# ThePixelExpert_ESP-32-WLED-Board__PCB__S.net
KiCad netlist of a schematic drawn in Altium Designer
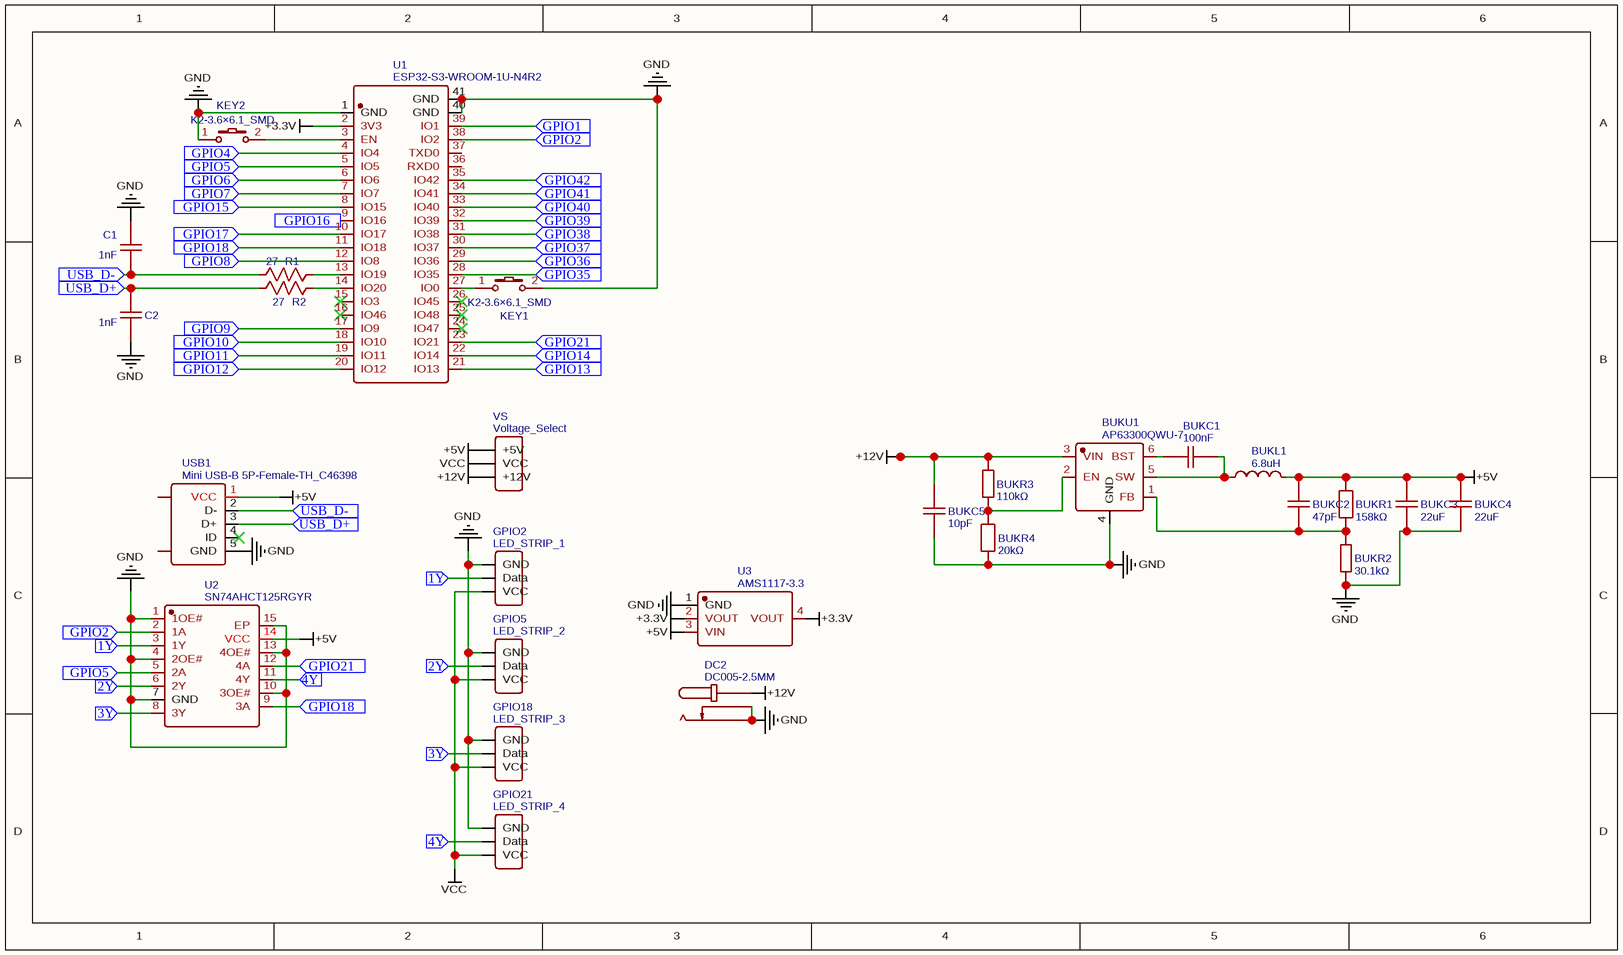
[diagram p0: ThePixelExpert_ESP-32-WLED-Board__PCB__Sheet_1_2025-09-09.schdoc]

(export (version "E")
  (design (tool "Eeschema 10.0.6"))
  (components
    (comp (ref "BUKC1")
      (value "100nF")
      (fields
        (field (name "MANUFACTURER") "FH(风华)")
        (field (name "MANUFACTURER PART") "0603B104J250NT")
        (field (name "CONTRIBUTOR") "lcsc")
      )
      (libsource (lib "altium-import") (part "root_0_100nF_"))
    )
    (comp (ref "BUKC2")
      (value "47pF")
      (fields
        (field (name "MANUFACTURER") "AIDE(爱迪电容)")
        (field (name "MANUFACTURER PART") "0603C0G470J500NT")
        (field (name "CONTRIBUTOR") "lcsc")
      )
      (libsource (lib "altium-import") (part "root_1_47pF_"))
    )
    (comp (ref "BUKC3")
      (value "22uF")
      (fields
        (field (name "MANUFACTURER") "Chinocera(华瓷)")
        (field (name "MANUFACTURER PART") "HGC0603R5226M160NTHJ")
        (field (name "CONTRIBUTOR") "lcsc")
      )
      (libsource (lib "altium-import") (part "root_1_22uF_"))
    )
    (comp (ref "BUKC4")
      (value "22uF")
      (fields
        (field (name "MANUFACTURER") "Chinocera(华瓷)")
        (field (name "MANUFACTURER PART") "HGC0603R5226M160NTHJ")
        (field (name "CONTRIBUTOR") "lcsc")
      )
      (libsource (lib "altium-import") (part "root_1_22uF_"))
    )
    (comp (ref "BUKC5")
      (value "10pF")
      (fields
        (field (name "MANUFACTURER") "YAGEO(国巨)")
        (field (name "MANUFACTURER PART") "CC0603FRNPO0BN100")
        (field (name "CONTRIBUTOR") "lcsc")
      )
      (libsource (lib "altium-import") (part "root_1_10pF_"))
    )
    (comp (ref "BUKL1")
      (value "6.8uH")
      (fields
        (field (name "MANUFACTURER") "FH(风华)")
        (field (name "MANUFACTURER PART") "CMP160808JE6R8MT")
        (field (name "CONTRIBUTOR") "LCSC")
      )
      (libsource (lib "altium-import") (part "root_0_6.8uH_"))
    )
    (comp (ref "BUKR1")
      (value "158kΩ")
      (fields
        (field (name "MANUFACTURER") "FOJAN(富捷)")
        (field (name "MANUFACTURER PART") "FRC0603F1583TS")
        (field (name "CONTRIBUTOR") "lcsc")
      )
      (libsource (lib "altium-import") (part "root_1_158kΩ_"))
    )
    (comp (ref "BUKR2")
      (value "30.1kΩ")
      (fields
        (field (name "MANUFACTURER") "Tyohm(幸亚电阻)")
        (field (name "MANUFACTURER PART") "RMC060330.1K1%N")
        (field (name "CONTRIBUTOR") "LCSC")
      )
      (libsource (lib "altium-import") (part "root_1_30.1kΩ_"))
    )
    (comp (ref "BUKR3")
      (value "110kΩ")
      (fields
        (field (name "MANUFACTURER") "YAGEO(国巨)")
        (field (name "MANUFACTURER PART") "RT0603BRD07110KL")
        (field (name "CONTRIBUTOR") "LCSC")
      )
      (libsource (lib "altium-import") (part "root_3_110kΩ_"))
    )
    (comp (ref "BUKR4")
      (value "20kΩ")
      (fields
        (field (name "MANUFACTURER") "YAGEO(国巨)")
        (field (name "MANUFACTURER PART") "RT0603CRE0720KL")
        (field (name "CONTRIBUTOR") "LCSC")
      )
      (libsource (lib "altium-import") (part "root_1_20kΩ_"))
    )
    (comp (ref "BUKU1")
      (value "AP63300QWU-7")
      (fields (field (name "MANUFACTURER") "DIODES(美台)") (field (name "CONTRIBUTOR") "lcsc"))
      (libsource (lib "altium-import") (part "root_0_AP63300QWU-7_"))
    )
    (comp (ref "C1")
      (value "1nF")
      (fields
        (field (name "MANUFACTURER PART") "CL10B102KB8NNNC")
        (field (name "MANUFACTURER") "Samsung Electro-Mechanics")
        (field (name "CONTRIBUTOR") "LCEDA_Lib")
      )
      (libsource (lib "altium-import") (part "root_1_1nF_"))
    )
    (comp (ref "C2")
      (value "1nF")
      (fields
        (field (name "MANUFACTURER PART") "CL10B102KB8NNNC")
        (field (name "MANUFACTURER") "Samsung Electro-Mechanics")
        (field (name "CONTRIBUTOR") "LCEDA_Lib")
      )
      (libsource (lib "altium-import") (part "root_1_1nF_"))
    )
    (comp (ref "DC2")
      (value "DC005-2.5MM")
      (fields (field (name "MANUFACTURER") "SOFNG(硕方)") (field (name "MANUFACTURER PART") "DC005-T25"))
      (libsource (lib "altium-import") (part "root_0_DC005-2.5MM_"))
    )
    (comp (ref "GPIO2")
      (value "LED_STRIP_1")
      (fields (field (name "MANUFACTURER") "BOOMELE(博穆精密)") (field (name "MANUFACTURER PART") "2.54-1*3P针"))
      (libsource (lib "altium-import") (part "root_0_LED_STRIP_1_"))
    )
    (comp (ref "GPIO5")
      (value "LED_STRIP_2")
      (fields (field (name "MANUFACTURER") "BOOMELE(博穆精密)") (field (name "MANUFACTURER PART") "2.54-1*3P针"))
      (libsource (lib "altium-import") (part "root_0_LED_STRIP_2_"))
    )
    (comp (ref "GPIO18")
      (value "LED_STRIP_3")
      (fields (field (name "MANUFACTURER") "BOOMELE(博穆精密)") (field (name "MANUFACTURER PART") "2.54-1*3P针"))
      (libsource (lib "altium-import") (part "root_0_LED_STRIP_3_"))
    )
    (comp (ref "GPIO21")
      (value "LED_STRIP_4")
      (fields (field (name "MANUFACTURER") "BOOMELE(博穆精密)") (field (name "MANUFACTURER PART") "2.54-1*3P针"))
      (libsource (lib "altium-import") (part "root_0_LED_STRIP_4_"))
    )
    (comp (ref "KEY1")
      (value "K2-3.6×6.1_SMD")
      (fields (field (name "MANUFACTURER PART") "K2-1107ST-A4SW-06") (field (name "CONTRIBUTOR") "LCEDA_Lib"))
      (libsource (lib "altium-import") (part "root_0_K2-3.6×6.1_SMD_"))
    )
    (comp (ref "KEY2")
      (value "K2-3.6×6.1_SMD")
      (fields (field (name "MANUFACTURER PART") "K2-1107ST-A4SW-06") (field (name "CONTRIBUTOR") "LCEDA_Lib"))
      (libsource (lib "altium-import") (part "root_0_K2-3.6×6.1_SMD_"))
    )
    (comp (ref "R1")
      (value "27")
      (fields
        (field (name "MANUFACTURER PART") "0603WAF270JT5E")
        (field (name "MANUFACTURER") "UNI-ROYAL(Uniroyal Elec)")
        (field (name "CONTRIBUTOR") "LCEDA_Lib")
      )
      (libsource (lib "altium-import") (part "root_0_27_"))
    )
    (comp (ref "R2")
      (value "27")
      (fields
        (field (name "MANUFACTURER PART") "0603WAF270JT5E")
        (field (name "MANUFACTURER") "UNI-ROYAL(Uniroyal Elec)")
        (field (name "CONTRIBUTOR") "LCEDA_Lib")
      )
      (libsource (lib "altium-import") (part "root_0_27_"))
    )
    (comp (ref "U1")
      (value "ESP32-S3-WROOM-1U-N4R2")
      (fields (field (name "MANUFACTURER") "ESPRESSIF(乐鑫)") (field (name "CONTRIBUTOR") "lcsc"))
      (libsource (lib "altium-import") (part "root_0_ESP32-S3-WROOM-1U-N4R2_"))
    )
    (comp (ref "U2")
      (value "SN74AHCT125RGYR")
      (fields (field (name "MANUFACTURER") "TI(德州仪器)") (field (name "CONTRIBUTOR") "LCSC"))
      (libsource (lib "altium-import") (part "root_0_SN74AHCT125RGYR_"))
    )
    (comp (ref "U3")
      (value "AMS1117-3.3")
      (fields (field (name "MANUFACTURER") "AMS"))
      (libsource (lib "altium-import") (part "root_0_AMS1117-3.3_"))
    )
    (comp (ref "USB1")
      (value "Mini USB-B 5P-Female-TH_C46398")
      (fields (field (name "MANUFACTURER") "精拓金") (field (name "MANUFACTURER PART") "920-462A2021D10102"))
      (libsource (lib "altium-import") (part "root_0_Mini USB-B 5P-Female-TH_C46398_"))
    )
    (comp (ref "VS")
      (value "Voltage_Select")
      (fields (field (name "MANUFACTURER") "BOOMELE(博穆精密)") (field (name "MANUFACTURER PART") "2.54-1*3P针"))
      (libsource (lib "altium-import") (part "root_0_Voltage_Select_"))
    )
  )
  (nets
    (net (code "1") (name "+3.3V") (class "Default")
      (node (ref "U1") (pin "2") (pinfunction "3V3_2") (pintype "passive"))
      (node (ref "U3") (pin "2") (pinfunction "VOUT_2") (pintype "passive"))
      (node (ref "U3") (pin "4") (pinfunction "VOUT_4") (pintype "passive"))
    )
    (net (code "2") (name "+5V") (class "Default")
      (node (ref "BUKC2") (pin "2") (pinfunction "2_2") (pintype "passive"))
      (node (ref "BUKC3") (pin "2") (pinfunction "2_2") (pintype "passive"))
      (node (ref "BUKC4") (pin "2") (pinfunction "2_2") (pintype "passive"))
      (node (ref "BUKL1") (pin "2") (pinfunction "2_2") (pintype "passive"))
      (node (ref "BUKR1") (pin "2") (pinfunction "2_2") (pintype "passive"))
      (node (ref "U2") (pin "14") (pinfunction "VCC_14") (pintype "passive"))
      (node (ref "U3") (pin "3") (pinfunction "VIN_3") (pintype "passive"))
      (node (ref "USB1") (pin "1") (pinfunction "VCC_1") (pintype "passive"))
      (node (ref "VS") (pin "1") (pinfunction "+5V_1") (pintype "passive"))
    )
    (net (code "3") (name "+12V") (class "Default")
      (node (ref "BUKC5") (pin "2") (pinfunction "2_2") (pintype "passive"))
      (node (ref "BUKR3") (pin "1") (pinfunction "1_1") (pintype "passive"))
      (node (ref "BUKU1") (pin "3") (pinfunction "VIN_3") (pintype "passive"))
      (node (ref "DC2") (pin "1") (pinfunction "1_1") (pintype "passive"))
      (node (ref "VS") (pin "3") (pinfunction "+12V_3") (pintype "passive"))
    )
    (net (code "4") (name "/1Y") (class "Default")
      (node (ref "GPIO2") (pin "2") (pinfunction "Data_2") (pintype "passive"))
      (node (ref "U2") (pin "3") (pinfunction "1Y_3") (pintype "passive"))
    )
    (net (code "5") (name "/2Y") (class "Default")
      (node (ref "GPIO5") (pin "2") (pinfunction "Data_2") (pintype "passive"))
      (node (ref "U2") (pin "6") (pinfunction "2Y_6") (pintype "passive"))
    )
    (net (code "6") (name "/3Y") (class "Default")
      (node (ref "GPIO18") (pin "2") (pinfunction "Data_2") (pintype "passive"))
      (node (ref "U2") (pin "8") (pinfunction "3Y_8") (pintype "passive"))
    )
    (net (code "7") (name "/4Y") (class "Default")
      (node (ref "GPIO21") (pin "2") (pinfunction "Data_2") (pintype "passive"))
      (node (ref "U2") (pin "11") (pinfunction "4Y_11") (pintype "passive"))
    )
    (net (code "8") (name "/GPIO1") (class "Default")
      (node (ref "U1") (pin "39") (pinfunction "IO1_39") (pintype "passive"))
    )
    (net (code "9") (name "/GPIO2") (class "Default")
      (node (ref "U1") (pin "38") (pinfunction "IO2_38") (pintype "passive"))
      (node (ref "U2") (pin "2") (pinfunction "1A_2") (pintype "passive"))
    )
    (net (code "10") (name "/GPIO4") (class "Default")
      (node (ref "U1") (pin "4") (pinfunction "IO4_4") (pintype "passive"))
    )
    (net (code "11") (name "/GPIO5") (class "Default")
      (node (ref "U1") (pin "5") (pinfunction "IO5_5") (pintype "passive"))
      (node (ref "U2") (pin "5") (pinfunction "2A_5") (pintype "passive"))
    )
    (net (code "12") (name "/GPIO6") (class "Default")
      (node (ref "U1") (pin "6") (pinfunction "IO6_6") (pintype "passive"))
    )
    (net (code "13") (name "/GPIO7") (class "Default")
      (node (ref "U1") (pin "7") (pinfunction "IO7_7") (pintype "passive"))
    )
    (net (code "14") (name "/GPIO8") (class "Default")
      (node (ref "U1") (pin "12") (pinfunction "IO8_12") (pintype "passive"))
    )
    (net (code "15") (name "/GPIO9") (class "Default")
      (node (ref "U1") (pin "17") (pinfunction "IO9_17") (pintype "passive"))
    )
    (net (code "16") (name "/GPIO10") (class "Default")
      (node (ref "U1") (pin "18") (pinfunction "IO10_18") (pintype "passive"))
    )
    (net (code "17") (name "/GPIO11") (class "Default")
      (node (ref "U1") (pin "19") (pinfunction "IO11_19") (pintype "passive"))
    )
    (net (code "18") (name "/GPIO12") (class "Default")
      (node (ref "U1") (pin "20") (pinfunction "IO12_20") (pintype "passive"))
    )
    (net (code "19") (name "/GPIO13") (class "Default")
      (node (ref "U1") (pin "21") (pinfunction "IO13_21") (pintype "passive"))
    )
    (net (code "20") (name "/GPIO14") (class "Default")
      (node (ref "U1") (pin "22") (pinfunction "IO14_22") (pintype "passive"))
    )
    (net (code "21") (name "/GPIO15") (class "Default")
      (node (ref "U1") (pin "8") (pinfunction "IO15_8") (pintype "passive"))
    )
    (net (code "22") (name "/GPIO16") (class "Default")
      (node (ref "U1") (pin "9") (pinfunction "IO16_9") (pintype "passive"))
    )
    (net (code "23") (name "/GPIO17") (class "Default")
      (node (ref "U1") (pin "10") (pinfunction "IO17_10") (pintype "passive"))
    )
    (net (code "24") (name "/GPIO18") (class "Default")
      (node (ref "U1") (pin "11") (pinfunction "IO18_11") (pintype "passive"))
      (node (ref "U2") (pin "9") (pinfunction "3A_9") (pintype "passive"))
    )
    (net (code "25") (name "/GPIO21") (class "Default")
      (node (ref "U1") (pin "23") (pinfunction "IO21_23") (pintype "passive"))
      (node (ref "U2") (pin "12") (pinfunction "4A_12") (pintype "passive"))
    )
    (net (code "26") (name "/GPIO35") (class "Default")
      (node (ref "U1") (pin "28") (pinfunction "IO35_28") (pintype "passive"))
    )
    (net (code "27") (name "/GPIO36") (class "Default")
      (node (ref "U1") (pin "29") (pinfunction "IO36_29") (pintype "passive"))
    )
    (net (code "28") (name "/GPIO37") (class "Default")
      (node (ref "U1") (pin "30") (pinfunction "IO37_30") (pintype "passive"))
    )
    (net (code "29") (name "/GPIO38") (class "Default")
      (node (ref "U1") (pin "31") (pinfunction "IO38_31") (pintype "passive"))
    )
    (net (code "30") (name "/GPIO39") (class "Default")
      (node (ref "U1") (pin "32") (pinfunction "IO39_32") (pintype "passive"))
    )
    (net (code "31") (name "/GPIO40") (class "Default")
      (node (ref "U1") (pin "33") (pinfunction "IO40_33") (pintype "passive"))
    )
    (net (code "32") (name "/GPIO41") (class "Default")
      (node (ref "U1") (pin "34") (pinfunction "IO41_34") (pintype "passive"))
    )
    (net (code "33") (name "/GPIO42") (class "Default")
      (node (ref "U1") (pin "35") (pinfunction "IO42_35") (pintype "passive"))
    )
    (net (code "34") (name "/USB_D+") (class "Default")
      (node (ref "C2") (pin "2") (pinfunction "2_2") (pintype "passive"))
      (node (ref "R2") (pin "1") (pinfunction "1_1") (pintype "passive"))
      (node (ref "USB1") (pin "3") (pinfunction "D+_3") (pintype "passive"))
    )
    (net (code "35") (name "/USB_D-") (class "Default")
      (node (ref "C1") (pin "1") (pinfunction "1_1") (pintype "passive"))
      (node (ref "R1") (pin "1") (pinfunction "1_1") (pintype "passive"))
      (node (ref "USB1") (pin "2") (pinfunction "D-_2") (pintype "passive"))
    )
    (net (code "36") (name "GND") (class "Default")
      (node (ref "BUKC3") (pin "1") (pinfunction "1_1") (pintype "passive"))
      (node (ref "BUKC4") (pin "1") (pinfunction "1_1") (pintype "passive"))
      (node (ref "BUKC5") (pin "1") (pinfunction "1_1") (pintype "passive"))
      (node (ref "BUKR2") (pin "1") (pinfunction "1_1") (pintype "passive"))
      (node (ref "BUKR4") (pin "1") (pinfunction "1_1") (pintype "passive"))
      (node (ref "BUKU1") (pin "4") (pinfunction "GND_4") (pintype "passive"))
      (node (ref "C1") (pin "2") (pinfunction "2_2") (pintype "passive"))
      (node (ref "C2") (pin "1") (pinfunction "1_1") (pintype "passive"))
      (node (ref "DC2") (pin "2") (pinfunction "2_2") (pintype "passive"))
      (node (ref "DC2") (pin "3") (pinfunction "3_3") (pintype "passive"))
      (node (ref "GPIO18") (pin "1") (pinfunction "GND_1") (pintype "passive"))
      (node (ref "GPIO2") (pin "1") (pinfunction "GND_1") (pintype "passive"))
      (node (ref "GPIO21") (pin "1") (pinfunction "GND_1") (pintype "passive"))
      (node (ref "GPIO5") (pin "1") (pinfunction "GND_1") (pintype "passive"))
      (node (ref "KEY1") (pin "2") (pinfunction "2_2") (pintype "passive"))
      (node (ref "KEY2") (pin "1") (pinfunction "1_1") (pintype "passive"))
      (node (ref "U1") (pin "1") (pinfunction "GND_1") (pintype "passive"))
      (node (ref "U1") (pin "40") (pinfunction "GND_40") (pintype "passive"))
      (node (ref "U1") (pin "41") (pinfunction "GND_41") (pintype "passive"))
      (node (ref "U2") (pin "1") (pinfunction "1OE#_1") (pintype "passive"))
      (node (ref "U2") (pin "10") (pinfunction "3OE#_10") (pintype "passive"))
      (node (ref "U2") (pin "13") (pinfunction "4OE#_13") (pintype "passive"))
      (node (ref "U2") (pin "15") (pinfunction "EP_15") (pintype "passive"))
      (node (ref "U2") (pin "4") (pinfunction "2OE#_4") (pintype "passive"))
      (node (ref "U2") (pin "7") (pinfunction "GND_7") (pintype "passive"))
      (node (ref "U3") (pin "1") (pinfunction "GND_1") (pintype "passive"))
      (node (ref "USB1") (pin "5") (pinfunction "GND_5") (pintype "passive"))
    )
    (net (code "37") (name "Net-(BUKU1-BST)") (class "Default")
      (node (ref "BUKC1") (pin "1") (pinfunction "1_1") (pintype "passive"))
      (node (ref "BUKU1") (pin "6") (pinfunction "BST_6") (pintype "passive"))
    )
    (net (code "38") (name "Net-(BUKU1-EN)") (class "Default")
      (node (ref "BUKR3") (pin "2") (pinfunction "2_2") (pintype "passive"))
      (node (ref "BUKR4") (pin "2") (pinfunction "2_2") (pintype "passive"))
      (node (ref "BUKU1") (pin "2") (pinfunction "EN_2") (pintype "passive"))
    )
    (net (code "39") (name "Net-(BUKU1-FB)") (class "Default")
      (node (ref "BUKC2") (pin "1") (pinfunction "1_1") (pintype "passive"))
      (node (ref "BUKR1") (pin "1") (pinfunction "1_1") (pintype "passive"))
      (node (ref "BUKR2") (pin "2") (pinfunction "2_2") (pintype "passive"))
      (node (ref "BUKU1") (pin "1") (pinfunction "FB_1") (pintype "passive"))
    )
    (net (code "40") (name "Net-(BUKU1-SW)") (class "Default")
      (node (ref "BUKC1") (pin "2") (pinfunction "2_2") (pintype "passive"))
      (node (ref "BUKL1") (pin "1") (pinfunction "1_1") (pintype "passive"))
      (node (ref "BUKU1") (pin "5") (pinfunction "SW_5") (pintype "passive"))
    )
    (net (code "41") (name "Net-(U1-EN)") (class "Default")
      (node (ref "KEY2") (pin "2") (pinfunction "2_2") (pintype "passive"))
      (node (ref "U1") (pin "3") (pinfunction "EN_3") (pintype "passive"))
    )
    (net (code "42") (name "Net-(U1-IO0)") (class "Default")
      (node (ref "KEY1") (pin "1") (pinfunction "1_1") (pintype "passive"))
      (node (ref "U1") (pin "27") (pinfunction "IO0_27") (pintype "passive"))
    )
    (net (code "43") (name "Net-(U1-IO19)") (class "Default")
      (node (ref "R1") (pin "2") (pinfunction "2_2") (pintype "passive"))
      (node (ref "U1") (pin "13") (pinfunction "IO19_13") (pintype "passive"))
    )
    (net (code "44") (name "Net-(U1-IO20)") (class "Default")
      (node (ref "R2") (pin "2") (pinfunction "2_2") (pintype "passive"))
      (node (ref "U1") (pin "14") (pinfunction "IO20_14") (pintype "passive"))
    )
    (net (code "45") (name "VCC") (class "Default")
      (node (ref "GPIO18") (pin "3") (pinfunction "VCC_3") (pintype "passive"))
      (node (ref "GPIO2") (pin "3") (pinfunction "VCC_3") (pintype "passive"))
      (node (ref "GPIO21") (pin "3") (pinfunction "VCC_3") (pintype "passive"))
      (node (ref "GPIO5") (pin "3") (pinfunction "VCC_3") (pintype "passive"))
      (node (ref "VS") (pin "2") (pinfunction "VCC_2") (pintype "passive"))
    )
    (net (code "46") (name "unconnected-(U1-IO3-Pad15)") (class "Default")
      (node (ref "U1") (pin "15") (pinfunction "IO3_15") (pintype "passive+no_connect"))
    )
    (net (code "47") (name "unconnected-(U1-IO45-Pad26)") (class "Default")
      (node (ref "U1") (pin "26") (pinfunction "IO45_26") (pintype "passive+no_connect"))
    )
    (net (code "48") (name "unconnected-(U1-IO46-Pad16)") (class "Default")
      (node (ref "U1") (pin "16") (pinfunction "IO46_16") (pintype "passive+no_connect"))
    )
    (net (code "49") (name "unconnected-(U1-IO47-Pad24)") (class "Default")
      (node (ref "U1") (pin "24") (pinfunction "IO47_24") (pintype "passive+no_connect"))
    )
    (net (code "50") (name "unconnected-(U1-IO48-Pad25)") (class "Default")
      (node (ref "U1") (pin "25") (pinfunction "IO48_25") (pintype "passive+no_connect"))
    )
    (net (code "51") (name "unconnected-(U1-RXD0-Pad36)") (class "Default")
      (node (ref "U1") (pin "36") (pinfunction "RXD0_36") (pintype "passive"))
    )
    (net (code "52") (name "unconnected-(U1-TXD0-Pad37)") (class "Default")
      (node (ref "U1") (pin "37") (pinfunction "TXD0_37") (pintype "passive"))
    )
    (net (code "53") (name "unconnected-(USB1-ID-Pad4)") (class "Default")
      (node (ref "USB1") (pin "4") (pinfunction "ID_4") (pintype "passive+no_connect"))
    )
    (net (code "54") (name "unconnected-(USB1-Pad0)") (class "Default")
      (node (ref "USB1") (pin "0") (pinfunction "0_0") (pintype "passive"))
    )
    (net (code "55") (name "unconnected-(USB1-Pad0)_1") (class "Default")
      (node (ref "USB1") (pin "0") (pinfunction "0_0") (pintype "passive"))
    )
  )
)
